# STC8H1K16.net
KiCad netlist of a schematic drawn in EasyEDA Pro
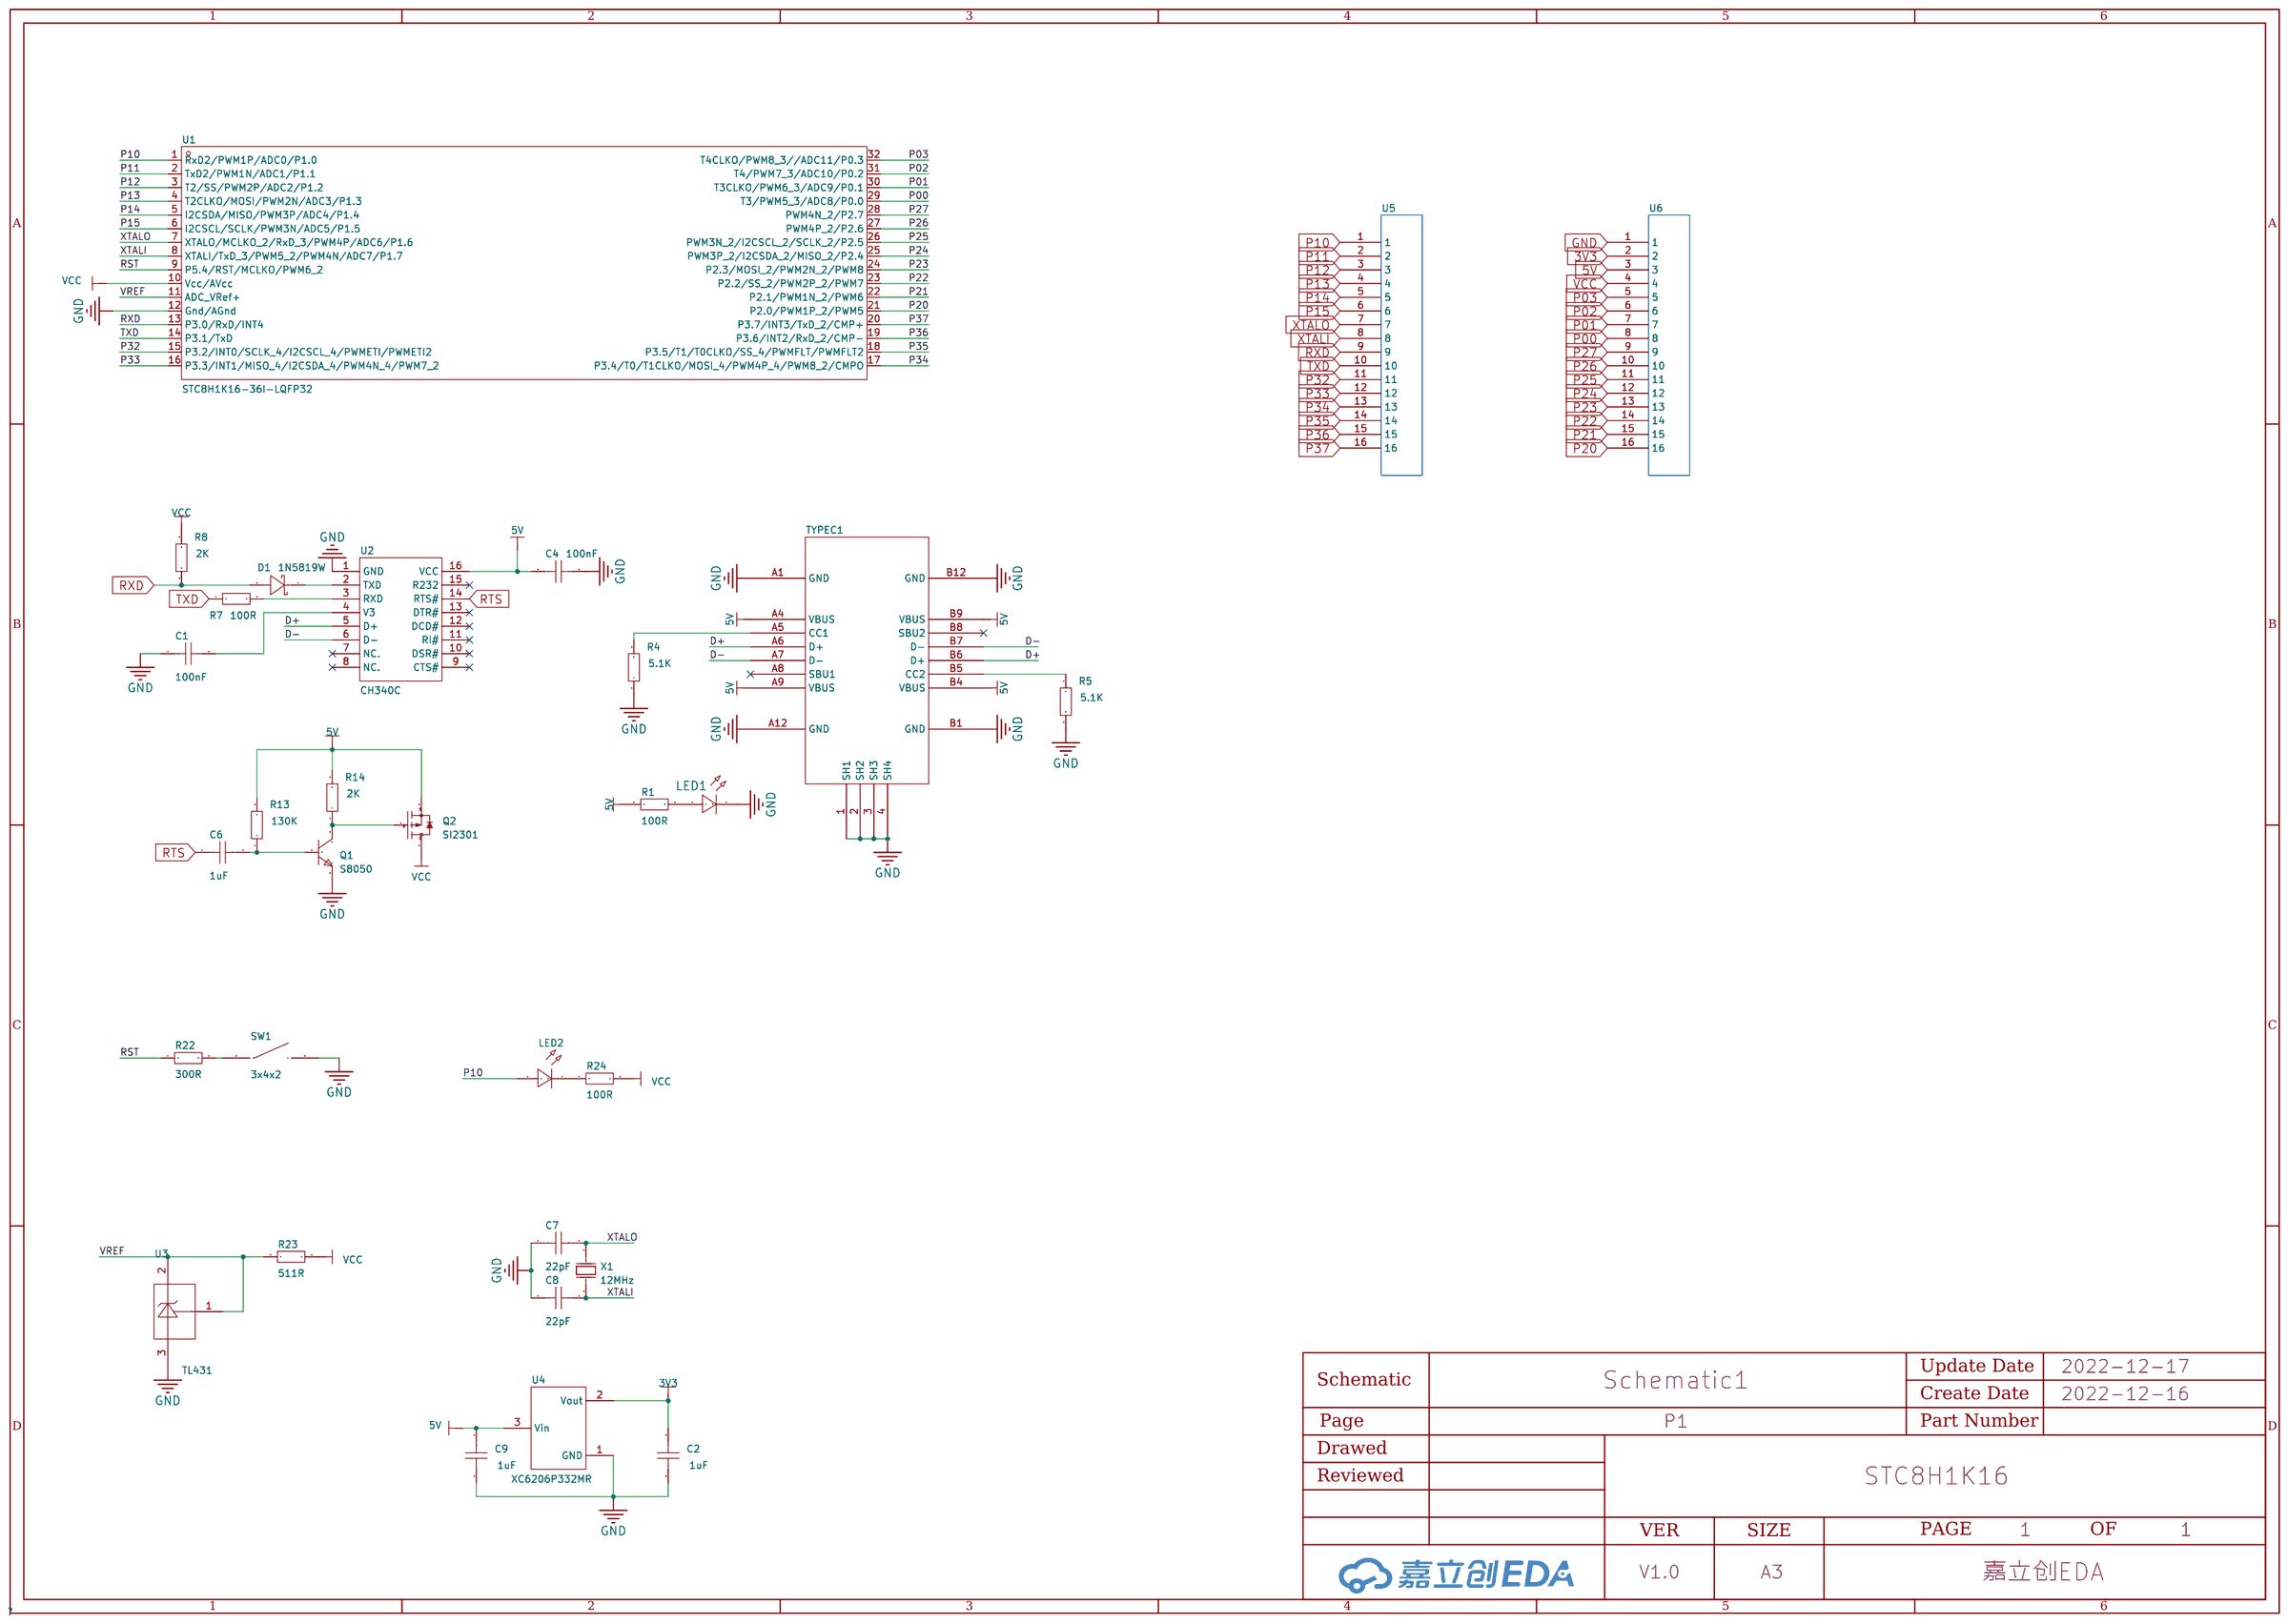
[diagram p0: schematic sheet]

(export (version "E")
  (design (tool "Eeschema 10.0.6"))
  (components
    (comp (ref "C1")
      (value "100nF")
      (footprint "easyedapro:C0603")
      (libsource (lib "easyedapro") (part "C1210X7R475K630NT"))
    )
    (comp (ref "C2")
      (value "1uF")
      (footprint "easyedapro:C0603")
      (libsource (lib "easyedapro") (part "CapAcitance"))
    )
    (comp (ref "C4")
      (value "100nF")
      (footprint "easyedapro:C0603")
      (libsource (lib "easyedapro") (part "C1210X7R475K630NT"))
    )
    (comp (ref "C6")
      (value "100nF")
      (footprint "easyedapro:C0603")
      (libsource (lib "easyedapro") (part "C1210X7R475K630NT"))
    )
    (comp (ref "C7")
      (value "22pF")
      (footprint "easyedapro:C0603")
      (libsource (lib "easyedapro") (part "CapAcitance"))
    )
    (comp (ref "C8")
      (value "22pF")
      (footprint "easyedapro:C0603")
      (libsource (lib "easyedapro") (part "CapAcitance"))
    )
    (comp (ref "C9")
      (value "1uF")
      (footprint "easyedapro:C0603")
      (libsource (lib "easyedapro") (part "CapAcitance"))
    )
    (comp (ref "D1")
      (value "1N5819W")
      (footprint "easyedapro:SOD-323_L1.7-W1.3-LS2.6-RD-1")
      (description "二极管配置:-;直流反向耐压(Vr):40V;平均整流电流(Io):350mA;正向压降(Vf):600mV@200mA;反向电流(Ir):5A@30V;")
      (fields (field (name "Manufacturer Part") "1N5819WS S4") (field (name "Manufacturer") "KUU"))
      (libsource (lib "easyedapro") (part "1N5819WS S4_C2939001"))
    )
    (comp (ref "LED1")
      (value "~")
      (footprint "easyedapro:LED0805-RD_RED")
      (libsource (lib "easyedapro") (part "LED_R"))
    )
    (comp (ref "LED2")
      (value "~")
      (footprint "easyedapro:LED_0805")
      (libsource (lib "easyedapro") (part "LED_G"))
    )
    (comp (ref "Q1")
      (value "S8050")
      (footprint "easyedapro:SOT-23-3_L2.9-W1.3-P1.90-LS2.4-BR")
      (description "NPN 25V 500mA 120-400 SOT-23")
      (fields (field (name "Manufacturer") "Doeshare(德芯)"))
      (libsource (lib "easyedapro") (part "S8050_C2931719"))
    )
    (comp (ref "Q2")
      (value "SI2301")
      (footprint "easyedapro:SOT-23-3_L2.9-W1.6-P1.90-LS2.8-BR")
      (fields (field (name "Manufacturer") "KUU"))
      (libsource (lib "easyedapro") (part "SI2301_C2985938"))
    )
    (comp (ref "R1") (value "10K") (footprint "easyedapro:R0603") (libsource (lib "easyedapro") (part "电阻")))
    (comp (ref "R4") (value "10K") (footprint "easyedapro:R0603") (libsource (lib "easyedapro") (part "电阻")))
    (comp (ref "R5") (value "10K") (footprint "easyedapro:R0603") (libsource (lib "easyedapro") (part "电阻")))
    (comp (ref "R7") (value "10K") (footprint "easyedapro:R0603") (libsource (lib "easyedapro") (part "电阻")))
    (comp (ref "R8") (value "10K") (footprint "easyedapro:R0603") (libsource (lib "easyedapro") (part "电阻")))
    (comp (ref "R13") (value "10K") (footprint "easyedapro:R0603") (libsource (lib "easyedapro") (part "电阻")))
    (comp (ref "R14") (value "10K") (footprint "easyedapro:R0603") (libsource (lib "easyedapro") (part "电阻")))
    (comp (ref "R22")
      (value "300R")
      (footprint "easyedapro:R0603")
      (libsource (lib "easyedapro") (part "电阻"))
    )
    (comp (ref "R23")
      (value "511R")
      (footprint "easyedapro:R0603")
      (libsource (lib "easyedapro") (part "电阻"))
    )
    (comp (ref "R24")
      (value "100R")
      (footprint "easyedapro:R0603")
      (libsource (lib "easyedapro") (part "电阻"))
    )
    (comp (ref "SW1")
      (value "3x4x2")
      (footprint "easyedapro:SW-SMD_L4.0-W2.9-LS5.0")
      (fields
        (field (name "Manufacturer Part") "TS-1185-C-A-B-B")
        (field (name "Manufacturer") "XKB Connectivity(中国星坤)")
      )
      (libsource (lib "easyedapro") (part "TS-1185-C-A-B-B"))
    )
    (comp (ref "TYPEC1")
      (value "~")
      (footprint "easyedapro:TypeC-16p")
      (libsource (lib "easyedapro") (part "Type C"))
    )
    (comp (ref "U1")
      (value "STC8H1K16-36I-LQFP32")
      (footprint "easyedapro:LQFP-32_L7.0-W7.0-P0.80-LS9.0-BL")
      (fields (field (name "Manufacturer") "STC(宏晶)"))
      (libsource (lib "easyedapro") (part "STC8H1K16-36I-LQFP32"))
    )
    (comp (ref "U2")
      (value "CH340C")
      (footprint "easyedapro:SOP-16_L10.0-W3.9-P1.27-LS6.0-BL")
      (description "类型:Transceiver;协议类别:USB 2.0;驱动器/接收器数:-;数据速率:2Mbps;")
      (fields (field (name "Manufacturer") "WCH(南京沁恒)"))
      (libsource (lib "easyedapro") (part "CH340C"))
    )
    (comp (ref "U3")
      (value "TL431")
      (footprint "easyedapro:SOT-23-3_L2.9-W1.3-P1.90-LS2.4-BR")
      (fields (field (name "Manufacturer") "YONGYUTAI(永裕泰)") (field (name "Tolerance") "1%"))
      (libsource (lib "easyedapro") (part "TL431_C2904832"))
    )
    (comp (ref "U4")
      (value "XC6206P332MR")
      (footprint "easyedapro:SOT-23-3_L2.9-W1.6-P1.90-LS2.8-BR")
      (description "输出类型:固定;输出极性:正;输出通道数:1;最大输入电压:6V;输出电压:3.3V;压差:680mV@(100mA);输出电流:200mA;电源纹波抑制比(PRSS):-;")
      (fields (field (name "Manufacturer") "TOREX(特瑞仕)"))
      (libsource (lib "easyedapro") (part "XC6206P332MR"))
    )
    (comp (ref "U5")
      (value "~")
      (footprint "easyedapro:Header-16P-2.54")
      (description "2.54 mm 排针")
      (libsource (lib "easyedapro") (part "Header-16P-2.54"))
    )
    (comp (ref "U6")
      (value "~")
      (footprint "easyedapro:Header-16P-2.54")
      (description "2.54 mm 排针")
      (libsource (lib "easyedapro") (part "Header-16P-2.54"))
    )
    (comp (ref "X1")
      (value "12MHz")
      (footprint "easyedapro:OSC-TH_L10.0-W4.5-P5.00")
      (description "晶振类型:49S晶振;频率:29.4912MHz;频率公差:±20ppm;频率稳定度:±30ppm;负载电容:20pF;工作温度:-20℃~+70℃;")
      (fields
        (field (name "Manufacturer Part") "X49SD294912MSD2SC")
        (field (name "Manufacturer") "YXC(扬兴晶振)")
      )
      (libsource (lib "easyedapro") (part "X49SD294912MSD2SC"))
    )
  )
  (nets
    (net (code "1") (name "/D+") (class "Default")
      (node (ref "TYPEC1") (pin "A6") (pinfunction "D+_A6") (pintype "input"))
      (node (ref "TYPEC1") (pin "B6") (pinfunction "D+_B6") (pintype "input"))
      (node (ref "U2") (pin "5") (pinfunction "D+_5") (pintype "input"))
    )
    (net (code "2") (name "/D-") (class "Default")
      (node (ref "TYPEC1") (pin "A7") (pinfunction "D-_A7") (pintype "input"))
      (node (ref "TYPEC1") (pin "B7") (pinfunction "D-_B7") (pintype "input"))
      (node (ref "U2") (pin "6") (pinfunction "D-_6") (pintype "input"))
    )
    (net (code "3") (name "/RST") (class "Default")
      (node (ref "R22") (pin "1") (pinfunction "1_1") (pintype "input"))
      (node (ref "U1") (pin "9") (pinfunction "P5.4/RST/MCLKO/PWM6_2_9") (pintype "input"))
    )
    (net (code "4") (name "/VREF") (class "Default")
      (node (ref "R23") (pin "1") (pinfunction "1_1") (pintype "input"))
      (node (ref "U1") (pin "11") (pinfunction "ADC_VRef+_11") (pintype "input"))
      (node (ref "U3") (pin "1") (pinfunction "REF_1") (pintype "input"))
      (node (ref "U3") (pin "2") (pinfunction "K_2") (pintype "input"))
    )
    (net (code "5") (name "3V3") (class "Default")
      (node (ref "C2") (pin "2") (pinfunction "2_2") (pintype "input"))
      (node (ref "U4") (pin "2") (pinfunction "Vout_2") (pintype "input"))
      (node (ref "U6") (pin "2") (pinfunction "2_2") (pintype "input"))
    )
    (net (code "6") (name "5V") (class "Default")
      (node (ref "C4") (pin "2") (pinfunction "2_2") (pintype "input"))
      (node (ref "C9") (pin "2") (pinfunction "2_2") (pintype "input"))
      (node (ref "Q2") (pin "2") (pinfunction "S_2") (pintype "input"))
      (node (ref "R1") (pin "1") (pinfunction "1_1") (pintype "input"))
      (node (ref "R13") (pin "2") (pinfunction "2_2") (pintype "input"))
      (node (ref "R14") (pin "2") (pinfunction "2_2") (pintype "input"))
      (node (ref "TYPEC1") (pin "A4") (pinfunction "VBUS_A4") (pintype "input"))
      (node (ref "TYPEC1") (pin "A9") (pinfunction "VBUS_A9") (pintype "input"))
      (node (ref "TYPEC1") (pin "B4") (pinfunction "VBUS_B4") (pintype "input"))
      (node (ref "TYPEC1") (pin "B9") (pinfunction "VBUS_B9") (pintype "input"))
      (node (ref "U2") (pin "16") (pinfunction "VCC_16") (pintype "input"))
      (node (ref "U4") (pin "3") (pinfunction "Vin_3") (pintype "input"))
      (node (ref "U6") (pin "3") (pinfunction "3_3") (pintype "input"))
    )
    (net (code "7") (name "GND") (class "Default")
      (node (ref "C1") (pin "1") (pinfunction "1_1") (pintype "input"))
      (node (ref "C2") (pin "1") (pinfunction "1_1") (pintype "input"))
      (node (ref "C4") (pin "1") (pinfunction "1_1") (pintype "input"))
      (node (ref "C7") (pin "1") (pinfunction "1_1") (pintype "input"))
      (node (ref "C8") (pin "1") (pinfunction "1_1") (pintype "input"))
      (node (ref "C9") (pin "1") (pinfunction "1_1") (pintype "input"))
      (node (ref "LED1") (pin "1") (pinfunction "C_1") (pintype "input"))
      (node (ref "Q1") (pin "2") (pinfunction "E_2") (pintype "input"))
      (node (ref "R4") (pin "1") (pinfunction "1_1") (pintype "input"))
      (node (ref "R5") (pin "2") (pinfunction "2_2") (pintype "input"))
      (node (ref "SW1") (pin "2") (pinfunction "2_2") (pintype "input"))
      (node (ref "TYPEC1") (pin "1") (pinfunction "SH1_1") (pintype "input"))
      (node (ref "TYPEC1") (pin "2") (pinfunction "SH2_2") (pintype "input"))
      (node (ref "TYPEC1") (pin "3") (pinfunction "SH3_3") (pintype "input"))
      (node (ref "TYPEC1") (pin "4") (pinfunction "SH4_4") (pintype "input"))
      (node (ref "TYPEC1") (pin "A1") (pinfunction "GND_A1") (pintype "input"))
      (node (ref "TYPEC1") (pin "A12") (pinfunction "GND_A12") (pintype "input"))
      (node (ref "TYPEC1") (pin "B1") (pinfunction "GND_B1") (pintype "input"))
      (node (ref "TYPEC1") (pin "B12") (pinfunction "GND_B12") (pintype "input"))
      (node (ref "U1") (pin "12") (pinfunction "Gnd/AGnd_12") (pintype "input"))
      (node (ref "U2") (pin "1") (pinfunction "GND_1") (pintype "input"))
      (node (ref "U3") (pin "3") (pinfunction "A_3") (pintype "input"))
      (node (ref "U4") (pin "1") (pinfunction "GND_1") (pintype "input"))
      (node (ref "U6") (pin "1") (pinfunction "1_1") (pintype "input"))
    )
    (net (code "8") (name "Net-(D1-K)") (class "Default")
      (node (ref "D1") (pin "1") (pinfunction "K_1") (pintype "input"))
      (node (ref "U2") (pin "2") (pinfunction "TXD_2") (pintype "input"))
    )
    (net (code "9") (name "Net-(LED1-A)") (class "Default")
      (node (ref "LED1") (pin "2") (pinfunction "A_2") (pintype "input"))
      (node (ref "R1") (pin "2") (pinfunction "2_2") (pintype "input"))
    )
    (net (code "10") (name "Net-(LED2-C)") (class "Default")
      (node (ref "LED2") (pin "1") (pinfunction "C_1") (pintype "input"))
      (node (ref "R24") (pin "1") (pinfunction "1_1") (pintype "input"))
    )
    (net (code "11") (name "Net-(Q1-B)") (class "Default")
      (node (ref "C6") (pin "2") (pinfunction "2_2") (pintype "input"))
      (node (ref "Q1") (pin "1") (pinfunction "B_1") (pintype "input"))
      (node (ref "R13") (pin "1") (pinfunction "1_1") (pintype "input"))
    )
    (net (code "12") (name "Net-(Q1-C)") (class "Default")
      (node (ref "Q1") (pin "3") (pinfunction "C_3") (pintype "input"))
      (node (ref "Q2") (pin "1") (pinfunction "G_1") (pintype "input"))
      (node (ref "R14") (pin "1") (pinfunction "1_1") (pintype "input"))
    )
    (net (code "13") (name "Net-(R22-Pad2)") (class "Default")
      (node (ref "R22") (pin "2") (pinfunction "2_2") (pintype "input"))
      (node (ref "SW1") (pin "1") (pinfunction "1_1") (pintype "input"))
    )
    (net (code "14") (name "Net-(TYPEC1-CC1)") (class "Default")
      (node (ref "R4") (pin "2") (pinfunction "2_2") (pintype "input"))
      (node (ref "TYPEC1") (pin "A5") (pinfunction "CC1_A5") (pintype "input"))
    )
    (net (code "15") (name "Net-(TYPEC1-CC2)") (class "Default")
      (node (ref "R5") (pin "1") (pinfunction "1_1") (pintype "input"))
      (node (ref "TYPEC1") (pin "B5") (pinfunction "CC2_B5") (pintype "input"))
    )
    (net (code "16") (name "Net-(U2-RXD)") (class "Default")
      (node (ref "R7") (pin "2") (pinfunction "2_2") (pintype "input"))
      (node (ref "U2") (pin "3") (pinfunction "RXD_3") (pintype "input"))
    )
    (net (code "17") (name "Net-(U2-V3)") (class "Default")
      (node (ref "C1") (pin "2") (pinfunction "2_2") (pintype "input"))
      (node (ref "U2") (pin "4") (pinfunction "V3_4") (pintype "input"))
    )
    (net (code "18") (name "P00") (class "Default")
      (node (ref "U1") (pin "29") (pinfunction "T3/PWM5_3/ADC8/P0.0_29") (pintype "input"))
      (node (ref "U6") (pin "8") (pinfunction "8_8") (pintype "input"))
    )
    (net (code "19") (name "P01") (class "Default")
      (node (ref "U1") (pin "30") (pinfunction "T3CLKO/PWM6_3/ADC9/P0.1_30") (pintype "input"))
      (node (ref "U6") (pin "7") (pinfunction "7_7") (pintype "input"))
    )
    (net (code "20") (name "P02") (class "Default")
      (node (ref "U1") (pin "31") (pinfunction "T4/PWM7_3/ADC10/P0.2_31") (pintype "input"))
      (node (ref "U6") (pin "6") (pinfunction "6_6") (pintype "input"))
    )
    (net (code "21") (name "P03") (class "Default")
      (node (ref "U1") (pin "32") (pinfunction "T4CLKO/PWM8_3//ADC11/P0.3_32") (pintype "input"))
      (node (ref "U6") (pin "5") (pinfunction "5_5") (pintype "input"))
    )
    (net (code "22") (name "P10") (class "Default")
      (node (ref "LED2") (pin "2") (pinfunction "A_2") (pintype "input"))
      (node (ref "U1") (pin "1") (pinfunction "RxD2/PWM1P/ADC0/P1.0_1") (pintype "input"))
      (node (ref "U5") (pin "1") (pinfunction "1_1") (pintype "input"))
    )
    (net (code "23") (name "P11") (class "Default")
      (node (ref "U1") (pin "2") (pinfunction "TxD2/PWM1N/ADC1/P1.1_2") (pintype "input"))
      (node (ref "U5") (pin "2") (pinfunction "2_2") (pintype "input"))
    )
    (net (code "24") (name "P12") (class "Default")
      (node (ref "U1") (pin "3") (pinfunction "T2/SS/PWM2P/ADC2/P1.2_3") (pintype "input"))
      (node (ref "U5") (pin "3") (pinfunction "3_3") (pintype "input"))
    )
    (net (code "25") (name "P13") (class "Default")
      (node (ref "U1") (pin "4") (pinfunction "T2CLKO/MOSI/PWM2N/ADC3/P1.3_4") (pintype "input"))
      (node (ref "U5") (pin "4") (pinfunction "4_4") (pintype "input"))
    )
    (net (code "26") (name "P14") (class "Default")
      (node (ref "U1") (pin "5") (pinfunction "I2CSDA/MISO/PWM3P/ADC4/P1.4_5") (pintype "input"))
      (node (ref "U5") (pin "5") (pinfunction "5_5") (pintype "input"))
    )
    (net (code "27") (name "P15") (class "Default")
      (node (ref "U1") (pin "6") (pinfunction "I2CSCL/SCLK/PWM3N/ADC5/P1.5_6") (pintype "input"))
      (node (ref "U5") (pin "6") (pinfunction "6_6") (pintype "input"))
    )
    (net (code "28") (name "P20") (class "Default")
      (node (ref "U1") (pin "21") (pinfunction "P2.0/PWM1P_2/PWM5_21") (pintype "input"))
      (node (ref "U6") (pin "16") (pinfunction "16_16") (pintype "input"))
    )
    (net (code "29") (name "P21") (class "Default")
      (node (ref "U1") (pin "22") (pinfunction "P2.1/PWM1N_2/PWM6_22") (pintype "input"))
      (node (ref "U6") (pin "15") (pinfunction "15_15") (pintype "input"))
    )
    (net (code "30") (name "P22") (class "Default")
      (node (ref "U1") (pin "23") (pinfunction "P2.2/SS_2/PWM2P_2/PWM7_23") (pintype "input"))
      (node (ref "U6") (pin "14") (pinfunction "14_14") (pintype "input"))
    )
    (net (code "31") (name "P23") (class "Default")
      (node (ref "U1") (pin "24") (pinfunction "P2.3/MOSI_2/PWM2N_2/PWM8_24") (pintype "input"))
      (node (ref "U6") (pin "13") (pinfunction "13_13") (pintype "input"))
    )
    (net (code "32") (name "P24") (class "Default")
      (node (ref "U1") (pin "25") (pinfunction "PWM3P_2/I2CSDA_2/MISO_2/P2.4_25") (pintype "input"))
      (node (ref "U6") (pin "12") (pinfunction "12_12") (pintype "input"))
    )
    (net (code "33") (name "P25") (class "Default")
      (node (ref "U1") (pin "26") (pinfunction "PWM3N_2/I2CSCL_2/SCLK_2/P2.5_26") (pintype "input"))
      (node (ref "U6") (pin "11") (pinfunction "11_11") (pintype "input"))
    )
    (net (code "34") (name "P26") (class "Default")
      (node (ref "U1") (pin "27") (pinfunction "PWM4P_2/P2.6_27") (pintype "input"))
      (node (ref "U6") (pin "10") (pinfunction "10_10") (pintype "input"))
    )
    (net (code "35") (name "P27") (class "Default")
      (node (ref "U1") (pin "28") (pinfunction "PWM4N_2/P2.7_28") (pintype "input"))
      (node (ref "U6") (pin "9") (pinfunction "9_9") (pintype "input"))
    )
    (net (code "36") (name "P32") (class "Default")
      (node (ref "U1") (pin "15") (pinfunction "P3.2/INT0/SCLK_4/I2CSCL_4/PWMETI/PWMETI2_15") (pintype "input"))
      (node (ref "U5") (pin "11") (pinfunction "11_11") (pintype "input"))
    )
    (net (code "37") (name "P33") (class "Default")
      (node (ref "U1") (pin "16") (pinfunction "P3.3/INT1/MISO_4/I2CSDA_4/PWM4N_4/PWM7_2_16") (pintype "input"))
      (node (ref "U5") (pin "12") (pinfunction "12_12") (pintype "input"))
    )
    (net (code "38") (name "P34") (class "Default")
      (node (ref "U1") (pin "17") (pinfunction "P3.4/T0/T1CLKO/MOSI_4/PWM4P_4/PWM8_2/CMPO_17") (pintype "input"))
      (node (ref "U5") (pin "13") (pinfunction "13_13") (pintype "input"))
    )
    (net (code "39") (name "P35") (class "Default")
      (node (ref "U1") (pin "18") (pinfunction "P3.5/T1/T0CLKO/SS_4/PWMFLT/PWMFLT2_18") (pintype "input"))
      (node (ref "U5") (pin "14") (pinfunction "14_14") (pintype "input"))
    )
    (net (code "40") (name "P36") (class "Default")
      (node (ref "U1") (pin "19") (pinfunction "P3.6/INT2/RxD_2/CMP-_19") (pintype "input"))
      (node (ref "U5") (pin "15") (pinfunction "15_15") (pintype "input"))
    )
    (net (code "41") (name "P37") (class "Default")
      (node (ref "U1") (pin "20") (pinfunction "P3.7/INT3/TxD_2/CMP+_20") (pintype "input"))
      (node (ref "U5") (pin "16") (pinfunction "16_16") (pintype "input"))
    )
    (net (code "42") (name "RTS") (class "Default")
      (node (ref "C6") (pin "1") (pinfunction "1_1") (pintype "input"))
      (node (ref "U2") (pin "14") (pinfunction "RTS#_14") (pintype "input"))
    )
    (net (code "43") (name "RXD") (class "Default")
      (node (ref "D1") (pin "2") (pinfunction "A_2") (pintype "input"))
      (node (ref "R8") (pin "1") (pinfunction "1_1") (pintype "input"))
      (node (ref "U1") (pin "13") (pinfunction "P3.0/RxD/INT4_13") (pintype "input"))
      (node (ref "U5") (pin "9") (pinfunction "9_9") (pintype "input"))
    )
    (net (code "44") (name "TXD") (class "Default")
      (node (ref "R7") (pin "1") (pinfunction "1_1") (pintype "input"))
      (node (ref "U1") (pin "14") (pinfunction "P3.1/TxD_14") (pintype "input"))
      (node (ref "U5") (pin "10") (pinfunction "10_10") (pintype "input"))
    )
    (net (code "45") (name "VCC") (class "Default")
      (node (ref "Q2") (pin "3") (pinfunction "D_3") (pintype "input"))
      (node (ref "R23") (pin "2") (pinfunction "2_2") (pintype "input"))
      (node (ref "R24") (pin "2") (pinfunction "2_2") (pintype "input"))
      (node (ref "R8") (pin "2") (pinfunction "2_2") (pintype "input"))
      (node (ref "U1") (pin "10") (pinfunction "Vcc/AVcc_10") (pintype "input"))
      (node (ref "U6") (pin "4") (pinfunction "4_4") (pintype "input"))
    )
    (net (code "46") (name "XTALI") (class "Default")
      (node (ref "C8") (pin "2") (pinfunction "2_2") (pintype "input"))
      (node (ref "U1") (pin "8") (pinfunction "XTALI/TxD_3/PWM5_2/PWM4N/ADC7/P1.7_8") (pintype "input"))
      (node (ref "U5") (pin "8") (pinfunction "8_8") (pintype "input"))
      (node (ref "X1") (pin "2") (pinfunction "OSC2_2") (pintype "input"))
    )
    (net (code "47") (name "XTALO") (class "Default")
      (node (ref "C7") (pin "2") (pinfunction "2_2") (pintype "input"))
      (node (ref "U1") (pin "7") (pinfunction "XTALO/MCLKO_2/RxD_3/PWM4P/ADC6/P1.6_7") (pintype "input"))
      (node (ref "U5") (pin "7") (pinfunction "7_7") (pintype "input"))
      (node (ref "X1") (pin "1") (pinfunction "OSC1_1") (pintype "input"))
    )
    (net (code "48") (name "unconnected-(TYPEC1-SBU1-PadA8)") (class "Default")
      (node (ref "TYPEC1") (pin "A8") (pinfunction "SBU1_A8") (pintype "input+no_connect"))
    )
    (net (code "49") (name "unconnected-(TYPEC1-SBU2-PadB8)") (class "Default")
      (node (ref "TYPEC1") (pin "B8") (pinfunction "SBU2_B8") (pintype "input+no_connect"))
    )
    (net (code "50") (name "unconnected-(U2-CTS#-Pad9)") (class "Default")
      (node (ref "U2") (pin "9") (pinfunction "CTS#_9") (pintype "input+no_connect"))
    )
    (net (code "51") (name "unconnected-(U2-DCD#-Pad12)") (class "Default")
      (node (ref "U2") (pin "12") (pinfunction "DCD#_12") (pintype "input+no_connect"))
    )
    (net (code "52") (name "unconnected-(U2-DSR#-Pad10)") (class "Default")
      (node (ref "U2") (pin "10") (pinfunction "DSR#_10") (pintype "input+no_connect"))
    )
    (net (code "53") (name "unconnected-(U2-DTR#-Pad13)") (class "Default")
      (node (ref "U2") (pin "13") (pinfunction "DTR#_13") (pintype "input+no_connect"))
    )
    (net (code "54") (name "unconnected-(U2-NC.-Pad7)") (class "Default")
      (node (ref "U2") (pin "7") (pinfunction "NC._7") (pintype "input+no_connect"))
    )
    (net (code "55") (name "unconnected-(U2-NC.-Pad8)") (class "Default")
      (node (ref "U2") (pin "8") (pinfunction "NC._8") (pintype "input+no_connect"))
    )
    (net (code "56") (name "unconnected-(U2-R232-Pad15)") (class "Default")
      (node (ref "U2") (pin "15") (pinfunction "R232_15") (pintype "input+no_connect"))
    )
    (net (code "57") (name "unconnected-(U2-RI#-Pad11)") (class "Default")
      (node (ref "U2") (pin "11") (pinfunction "RI#_11") (pintype "input+no_connect"))
    )
  )
)
